# Server_wire_chart.net
KiCad netlist of a schematic drawn in EAGLE
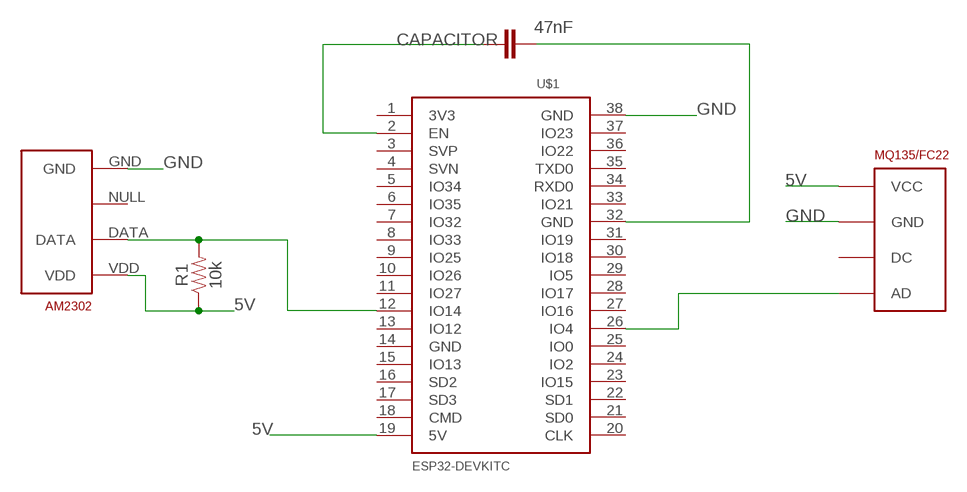
[diagram p0: schematic, sheet 1]

(export (version "E")
  (design (tool "Eeschema 10.0.6"))
  (components
    (comp (ref "AM2302")
      (value "RHT03_DHT-22_AM2302")
      (footprint "eagle-import:RHT03_DHT-22")
      (libsource (lib "eagle-import") (part "RHT03_DHT-22_AM2302"))
    )
    (comp (ref "CAPACITOR")
      (value "47nF")
      (footprint "eagle-import:C2.5-3")
      (libsource (lib "eagle-import") (part "C2,5-3"))
    )
    (comp (ref "MQ135/FC22")
      (value "MQ")
      (footprint "eagle-import:RHT03_DHT-22")
      (libsource (lib "eagle-import") (part "MQ"))
    )
    (comp (ref "R1")
      (value "10k")
      (footprint "eagle-import:0402")
      (libsource (lib "eagle-import") (part "10KOHM-0402-1/16W-1%"))
    )
    (comp (ref "U$1")
      (value "ESP32DEVKITC")
      (footprint "eagle-import:ESP32-DEVKITC")
      (libsource (lib "eagle-import") (part "ESP32DEVKITC"))
    )
  )
  (nets
    (net (code "1") (name "/5V") (class "Default")
      (node (ref "AM2302") (pin "VDD") (pinfunction "VDD_VDD") (pintype "power_in"))
      (node (ref "MQ135/FC22") (pin "VDD") (pinfunction "VCC_VDD") (pintype "power_in"))
      (node (ref "R1") (pin "1") (pinfunction "1_1") (pintype "passive"))
      (node (ref "U$1") (pin "19") (pinfunction "5V_19") (pintype "bidirectional"))
    )
    (net (code "2") (name "/DC") (class "Default")
      (node (ref "MQ135/FC22") (pin "NULL") (pinfunction "DC_NULL") (pintype "power_in"))
    )
    (net (code "3") (name "/GND") (class "Default")
      (node (ref "AM2302") (pin "GND") (pinfunction "GND_GND") (pintype "power_in"))
      (node (ref "MQ135/FC22") (pin "DATA") (pinfunction "GND_DATA") (pintype "bidirectional"))
      (node (ref "U$1") (pin "38") (pinfunction "GND_38") (pintype "bidirectional"))
    )
    (net (code "4") (name "Net-(CAPACITOR-Pad2)") (class "Default")
      (node (ref "CAPACITOR") (pin "2") (pinfunction "2_2") (pintype "passive"))
      (node (ref "U$1") (pin "32") (pinfunction "GND_32") (pintype "bidirectional"))
    )
    (net (code "5") (name "Net-(MQ135/FC22-AD)") (class "Default")
      (node (ref "MQ135/FC22") (pin "GND") (pinfunction "AD_GND") (pintype "power_in"))
      (node (ref "U$1") (pin "26") (pinfunction "IO4_26") (pintype "bidirectional"))
    )
    (net (code "6") (name "Net-(U$1-EN)") (class "Default")
      (node (ref "CAPACITOR") (pin "1") (pinfunction "1_1") (pintype "passive"))
      (node (ref "U$1") (pin "2") (pinfunction "EN_2") (pintype "bidirectional"))
    )
    (net (code "7") (name "Net-(U$1-IO14)") (class "Default")
      (node (ref "AM2302") (pin "DATA") (pinfunction "DATA_DATA") (pintype "bidirectional"))
      (node (ref "R1") (pin "2") (pinfunction "2_2") (pintype "passive"))
      (node (ref "U$1") (pin "12") (pinfunction "IO14_12") (pintype "bidirectional"))
    )
    (net (code "8") (name "unconnected-(AM2302-PadNULL)") (class "Default")
      (node (ref "AM2302") (pin "NULL") (pinfunction "NULL_NULL") (pintype "no_connect"))
    )
    (net (code "9") (name "unconnected-(U$1-3V3-Pad1)") (class "Default")
      (node (ref "U$1") (pin "1") (pinfunction "3V3_1") (pintype "bidirectional"))
    )
    (net (code "10") (name "unconnected-(U$1-CLK-Pad20)") (class "Default")
      (node (ref "U$1") (pin "20") (pinfunction "CLK_20") (pintype "bidirectional"))
    )
    (net (code "11") (name "unconnected-(U$1-CMD-Pad18)") (class "Default")
      (node (ref "U$1") (pin "18") (pinfunction "CMD_18") (pintype "bidirectional"))
    )
    (net (code "12") (name "unconnected-(U$1-GND-Pad14)") (class "Default")
      (node (ref "U$1") (pin "14") (pinfunction "GND_14") (pintype "bidirectional"))
    )
    (net (code "13") (name "unconnected-(U$1-IO0-Pad25)") (class "Default")
      (node (ref "U$1") (pin "25") (pinfunction "IO0_25") (pintype "bidirectional"))
    )
    (net (code "14") (name "unconnected-(U$1-IO2-Pad24)") (class "Default")
      (node (ref "U$1") (pin "24") (pinfunction "IO2_24") (pintype "bidirectional"))
    )
    (net (code "15") (name "unconnected-(U$1-IO5-Pad29)") (class "Default")
      (node (ref "U$1") (pin "29") (pinfunction "IO5_29") (pintype "bidirectional"))
    )
    (net (code "16") (name "unconnected-(U$1-IO12-Pad13)") (class "Default")
      (node (ref "U$1") (pin "13") (pinfunction "IO12_13") (pintype "bidirectional"))
    )
    (net (code "17") (name "unconnected-(U$1-IO13-Pad15)") (class "Default")
      (node (ref "U$1") (pin "15") (pinfunction "IO13_15") (pintype "bidirectional"))
    )
    (net (code "18") (name "unconnected-(U$1-IO15-Pad23)") (class "Default")
      (node (ref "U$1") (pin "23") (pinfunction "IO15_23") (pintype "bidirectional"))
    )
    (net (code "19") (name "unconnected-(U$1-IO16-Pad27)") (class "Default")
      (node (ref "U$1") (pin "27") (pinfunction "IO16_27") (pintype "bidirectional"))
    )
    (net (code "20") (name "unconnected-(U$1-IO17-Pad28)") (class "Default")
      (node (ref "U$1") (pin "28") (pinfunction "IO17_28") (pintype "bidirectional"))
    )
    (net (code "21") (name "unconnected-(U$1-IO18-Pad30)") (class "Default")
      (node (ref "U$1") (pin "30") (pinfunction "IO18_30") (pintype "bidirectional"))
    )
    (net (code "22") (name "unconnected-(U$1-IO19-Pad31)") (class "Default")
      (node (ref "U$1") (pin "31") (pinfunction "IO19_31") (pintype "bidirectional"))
    )
    (net (code "23") (name "unconnected-(U$1-IO21-Pad33)") (class "Default")
      (node (ref "U$1") (pin "33") (pinfunction "IO21_33") (pintype "bidirectional"))
    )
    (net (code "24") (name "unconnected-(U$1-IO22-Pad36)") (class "Default")
      (node (ref "U$1") (pin "36") (pinfunction "IO22_36") (pintype "bidirectional"))
    )
    (net (code "25") (name "unconnected-(U$1-IO23-Pad37)") (class "Default")
      (node (ref "U$1") (pin "37") (pinfunction "IO23_37") (pintype "bidirectional"))
    )
    (net (code "26") (name "unconnected-(U$1-IO25-Pad9)") (class "Default")
      (node (ref "U$1") (pin "9") (pinfunction "IO25_9") (pintype "bidirectional"))
    )
    (net (code "27") (name "unconnected-(U$1-IO26-Pad10)") (class "Default")
      (node (ref "U$1") (pin "10") (pinfunction "IO26_10") (pintype "bidirectional"))
    )
    (net (code "28") (name "unconnected-(U$1-IO27-Pad11)") (class "Default")
      (node (ref "U$1") (pin "11") (pinfunction "IO27_11") (pintype "bidirectional"))
    )
    (net (code "29") (name "unconnected-(U$1-IO32-Pad7)") (class "Default")
      (node (ref "U$1") (pin "7") (pinfunction "IO32_7") (pintype "bidirectional"))
    )
    (net (code "30") (name "unconnected-(U$1-IO33-Pad8)") (class "Default")
      (node (ref "U$1") (pin "8") (pinfunction "IO33_8") (pintype "bidirectional"))
    )
    (net (code "31") (name "unconnected-(U$1-IO34-Pad5)") (class "Default")
      (node (ref "U$1") (pin "5") (pinfunction "IO34_5") (pintype "bidirectional"))
    )
    (net (code "32") (name "unconnected-(U$1-IO35-Pad6)") (class "Default")
      (node (ref "U$1") (pin "6") (pinfunction "IO35_6") (pintype "bidirectional"))
    )
    (net (code "33") (name "unconnected-(U$1-RXD0-Pad34)") (class "Default")
      (node (ref "U$1") (pin "34") (pinfunction "RXD0_34") (pintype "bidirectional"))
    )
    (net (code "34") (name "unconnected-(U$1-SD0-Pad21)") (class "Default")
      (node (ref "U$1") (pin "21") (pinfunction "SD0_21") (pintype "bidirectional"))
    )
    (net (code "35") (name "unconnected-(U$1-SD1-Pad22)") (class "Default")
      (node (ref "U$1") (pin "22") (pinfunction "SD1_22") (pintype "bidirectional"))
    )
    (net (code "36") (name "unconnected-(U$1-SD2-Pad16)") (class "Default")
      (node (ref "U$1") (pin "16") (pinfunction "SD2_16") (pintype "bidirectional"))
    )
    (net (code "37") (name "unconnected-(U$1-SD3-Pad17)") (class "Default")
      (node (ref "U$1") (pin "17") (pinfunction "SD3_17") (pintype "bidirectional"))
    )
    (net (code "38") (name "unconnected-(U$1-SVN-Pad4)") (class "Default")
      (node (ref "U$1") (pin "4") (pinfunction "SVN_4") (pintype "bidirectional"))
    )
    (net (code "39") (name "unconnected-(U$1-SVP-Pad3)") (class "Default")
      (node (ref "U$1") (pin "3") (pinfunction "SVP_3") (pintype "bidirectional"))
    )
    (net (code "40") (name "unconnected-(U$1-TXD0-Pad35)") (class "Default")
      (node (ref "U$1") (pin "35") (pinfunction "TXD0_35") (pintype "bidirectional"))
    )
  )
)
